# wsb2812-adapter.net
KiCad netlist of a schematic drawn in EAGLE
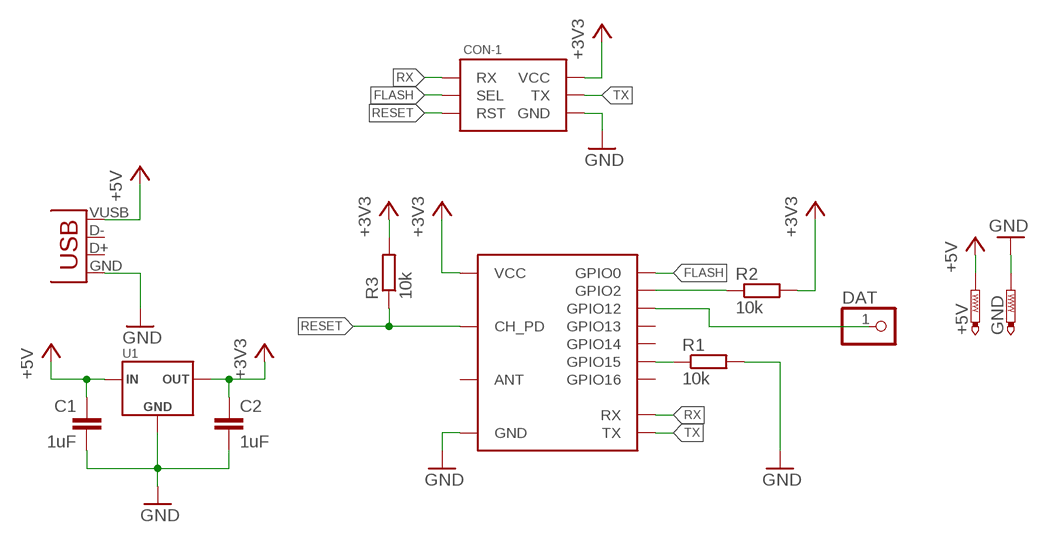
[diagram p0: schematic, sheet 1]

(export (version "E")
  (design (tool "Eeschema 10.0.6"))
  (components
    (comp (ref "+5V")
      (value "PTR1PAD1-20")
      (footprint "eagle-import:P1-20")
      (libsource (lib "eagle-import") (part "PTR1PAD1-20"))
    )
    (comp (ref "C1")
      (value "1uF")
      (footprint "eagle-import:C0805")
      (libsource (lib "eagle-import") (part "C-EUC0805"))
    )
    (comp (ref "C2")
      (value "1uF")
      (footprint "eagle-import:C0805")
      (libsource (lib "eagle-import") (part "C-EUC0805"))
    )
    (comp (ref "CON-1")
      (value "ESP8266-6_PIN-POGO")
      (footprint "eagle-import:POGO-1.27-6_PIN-MADWORM")
      (libsource (lib "eagle-import") (part "ESP8266-6_PIN-POGO"))
    )
    (comp (ref "CON1")
      (value "USBMICRO-NO_CENTER")
      (footprint "eagle-import:USB-MICRO-SMD-NO_CENTER")
      (libsource (lib "eagle-import") (part "USBMICRO-NO_CENTER"))
    )
    (comp (ref "DAT")
      (value "PINHD-1X1")
      (footprint "eagle-import:1X01")
      (libsource (lib "eagle-import") (part "PINHD-1X1"))
    )
    (comp (ref "GND")
      (value "PTR1PAD1-20")
      (footprint "eagle-import:P1-20")
      (libsource (lib "eagle-import") (part "PTR1PAD1-20"))
    )
    (comp (ref "R1")
      (value "10k")
      (footprint "eagle-import:R0603")
      (libsource (lib "eagle-import") (part "R-EU_R0603"))
    )
    (comp (ref "R2")
      (value "10k")
      (footprint "eagle-import:R0603")
      (libsource (lib "eagle-import") (part "R-EU_R0603"))
    )
    (comp (ref "R3")
      (value "10k")
      (footprint "eagle-import:R0603")
      (libsource (lib "eagle-import") (part "R-EU_R0603"))
    )
    (comp (ref "U$1")
      (value "ESP8266-03")
      (footprint "eagle-import:ESP8266-ESP-03")
      (libsource (lib "eagle-import") (part "ESP8266-03"))
    )
    (comp (ref "U1")
      (value "REGULATOR-XC6206SOT23")
      (footprint "eagle-import:SOT23")
      (libsource (lib "eagle-import") (part "REGULATOR-XC6206SOT23"))
    )
  )
  (nets
    (net (code "1") (name "+3V3") (class "Default")
      (node (ref "C2") (pin "1") (pinfunction "1_1") (pintype "passive"))
      (node (ref "CON-1") (pin "P$2") (pinfunction "VCC_P$2") (pintype "power_in"))
      (node (ref "R2") (pin "2") (pinfunction "2_2") (pintype "passive"))
      (node (ref "R3") (pin "2") (pinfunction "2_2") (pintype "passive"))
      (node (ref "U$1") (pin "P$8") (pinfunction "VCC_P$8") (pintype "bidirectional"))
      (node (ref "U1") (pin "P$2") (pinfunction "OUT_P$2") (pintype "bidirectional"))
    )
    (net (code "2") (name "+5V") (class "Default")
      (node (ref "+5V") (pin "TP") (pinfunction "TP_TP") (pintype "input"))
      (node (ref "C1") (pin "1") (pinfunction "1_1") (pintype "passive"))
      (node (ref "CON1") (pin "VUSB") (pinfunction "VBUS_VUSB") (pintype "bidirectional"))
      (node (ref "U1") (pin "P$3") (pinfunction "IN_P$3") (pintype "bidirectional"))
    )
    (net (code "3") (name "FLASH") (class "Default")
      (node (ref "CON-1") (pin "P$3") (pinfunction "SEL_P$3") (pintype "bidirectional"))
      (node (ref "U$1") (pin "P$14") (pinfunction "GPIO0_P$14") (pintype "bidirectional"))
    )
    (net (code "4") (name "GND") (class "Default")
      (node (ref "C1") (pin "2") (pinfunction "2_2") (pintype "passive"))
      (node (ref "C2") (pin "2") (pinfunction "2_2") (pintype "passive"))
      (node (ref "CON-1") (pin "P$6") (pinfunction "GND_P$6") (pintype "power_in"))
      (node (ref "CON1") (pin "GND") (pinfunction "GND_GND") (pintype "bidirectional"))
      (node (ref "GND") (pin "TP") (pinfunction "TP_TP") (pintype "input"))
      (node (ref "R1") (pin "2") (pinfunction "2_2") (pintype "passive"))
      (node (ref "U$1") (pin "P$1") (pinfunction "GND_P$1") (pintype "bidirectional"))
      (node (ref "U1") (pin "P$1") (pinfunction "GND_P$1") (pintype "bidirectional"))
    )
    (net (code "5") (name "Net-(U$1-GPIO2)") (class "Default")
      (node (ref "R2") (pin "1") (pinfunction "1_1") (pintype "passive"))
      (node (ref "U$1") (pin "P$13") (pinfunction "GPIO2_P$13") (pintype "bidirectional"))
    )
    (net (code "6") (name "Net-(U$1-GPIO12)") (class "Default")
      (node (ref "DAT") (pin "1") (pinfunction "1_1") (pintype "passive"))
      (node (ref "U$1") (pin "P$10") (pinfunction "GPIO12_P$10") (pintype "bidirectional"))
    )
    (net (code "7") (name "Net-(U$1-GPIO15)") (class "Default")
      (node (ref "R1") (pin "1") (pinfunction "1_1") (pintype "passive"))
      (node (ref "U$1") (pin "P$12") (pinfunction "GPIO15_P$12") (pintype "bidirectional"))
    )
    (net (code "8") (name "RESET") (class "Default")
      (node (ref "CON-1") (pin "P$5") (pinfunction "RST_P$5") (pintype "bidirectional"))
      (node (ref "R3") (pin "1") (pinfunction "1_1") (pintype "passive"))
      (node (ref "U$1") (pin "P$6") (pinfunction "CH_PD_P$6") (pintype "bidirectional"))
    )
    (net (code "9") (name "RX") (class "Default")
      (node (ref "CON-1") (pin "P$1") (pinfunction "RX_P$1") (pintype "bidirectional"))
      (node (ref "U$1") (pin "P$4") (pinfunction "RX_P$4") (pintype "bidirectional"))
    )
    (net (code "10") (name "TX") (class "Default")
      (node (ref "CON-1") (pin "P$4") (pinfunction "TX_P$4") (pintype "bidirectional"))
      (node (ref "U$1") (pin "P$3") (pinfunction "TX_P$3") (pintype "bidirectional"))
    )
    (net (code "11") (name "unconnected-(CON1-PadD+)") (class "Default")
      (node (ref "CON1") (pin "D+") (pinfunction "D+_D+") (pintype "bidirectional"))
    )
    (net (code "12") (name "unconnected-(CON1-PadD-)") (class "Default")
      (node (ref "CON1") (pin "D-") (pinfunction "D-_D-") (pintype "bidirectional"))
    )
    (net (code "13") (name "unconnected-(U$1-ANT-PadP$7)") (class "Default")
      (node (ref "U$1") (pin "P$7") (pinfunction "ANT_P$7") (pintype "bidirectional"))
    )
    (net (code "14") (name "unconnected-(U$1-GPIO13-PadP$11)") (class "Default")
      (node (ref "U$1") (pin "P$11") (pinfunction "GPIO13_P$11") (pintype "bidirectional"))
    )
    (net (code "15") (name "unconnected-(U$1-GPIO14-PadP$9)") (class "Default")
      (node (ref "U$1") (pin "P$9") (pinfunction "GPIO14_P$9") (pintype "bidirectional"))
    )
    (net (code "16") (name "unconnected-(U$1-GPIO16-PadP$5)") (class "Default")
      (node (ref "U$1") (pin "P$5") (pinfunction "GPIO16_P$5") (pintype "bidirectional"))
    )
  )
)
